# nuc10breakout.net
KiCad netlist of a schematic drawn in EAGLE
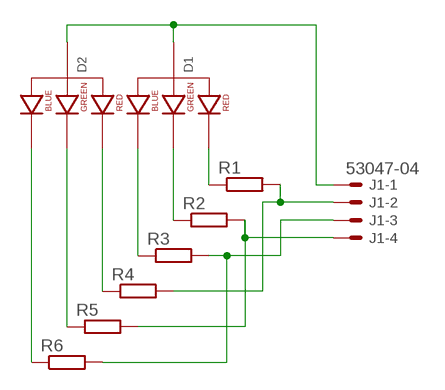
[diagram p0: schematic, sheet 1]

(export (version "E")
  (design (tool "Eeschema 10.0.6"))
  (components
    (comp (ref "D1")
      (value "LED-RGB-CA-THRUDIFFUSE")
      (footprint "eagle-import:LED-RGB-THRU")
      (libsource (lib "eagle-import") (part "LED-RGB-CA-THRUDIFFUSE"))
    )
    (comp (ref "D2")
      (value "LED-RGB-CA-THRUDIFFUSE")
      (footprint "eagle-import:LED-RGB-THRU")
      (libsource (lib "eagle-import") (part "LED-RGB-CA-THRUDIFFUSE"))
    )
    (comp (ref "J1")
      (value "53047-04")
      (footprint "eagle-import:53047-04")
      (fields (field (name "MF") "WALDOM/MOLEX") (field (name "MPN") "53047-0410"))
      (libsource (lib "eagle-import") (part "53?-04047"))
    )
    (comp (ref "R1")
      (value "R-EU_0204/5")
      (footprint "eagle-import:0204_5")
      (libsource (lib "eagle-import") (part "R-EU_0204/5"))
    )
    (comp (ref "R2")
      (value "R-EU_0204/5")
      (footprint "eagle-import:0204_5")
      (libsource (lib "eagle-import") (part "R-EU_0204/5"))
    )
    (comp (ref "R3")
      (value "R-EU_0204/5")
      (footprint "eagle-import:0204_5")
      (libsource (lib "eagle-import") (part "R-EU_0204/5"))
    )
    (comp (ref "R4")
      (value "R-EU_0204/5")
      (footprint "eagle-import:0204_5")
      (libsource (lib "eagle-import") (part "R-EU_0204/5"))
    )
    (comp (ref "R5")
      (value "R-EU_0204/5")
      (footprint "eagle-import:0204_5")
      (libsource (lib "eagle-import") (part "R-EU_0204/5"))
    )
    (comp (ref "R6")
      (value "R-EU_0204/5")
      (footprint "eagle-import:0204_5")
      (libsource (lib "eagle-import") (part "R-EU_0204/5"))
    )
  )
  (nets
    (net (code "1") (name "Net-(D1-ANODE)") (class "Default")
      (node (ref "D1") (pin "2") (pinfunction "ANODE_2") (pintype "bidirectional"))
      (node (ref "D2") (pin "2") (pinfunction "ANODE_2") (pintype "bidirectional"))
      (node (ref "J1") (pin "1") (pinfunction "S_1") (pintype "passive"))
    )
    (net (code "2") (name "Net-(D1-BLUE_CATHODE)") (class "Default")
      (node (ref "D1") (pin "4") (pinfunction "BLUE_CATHODE_4") (pintype "bidirectional"))
      (node (ref "R3") (pin "1") (pinfunction "1_1") (pintype "passive"))
    )
    (net (code "3") (name "Net-(D1-GREEN_CATHODE)") (class "Default")
      (node (ref "D1") (pin "3") (pinfunction "GREEN_CATHODE_3") (pintype "bidirectional"))
      (node (ref "R2") (pin "1") (pinfunction "1_1") (pintype "passive"))
    )
    (net (code "4") (name "Net-(D1-RED_CATHODE)") (class "Default")
      (node (ref "D1") (pin "1") (pinfunction "RED_CATHODE_1") (pintype "bidirectional"))
      (node (ref "R1") (pin "1") (pinfunction "1_1") (pintype "passive"))
    )
    (net (code "5") (name "Net-(D2-BLUE_CATHODE)") (class "Default")
      (node (ref "D2") (pin "4") (pinfunction "BLUE_CATHODE_4") (pintype "bidirectional"))
      (node (ref "R6") (pin "1") (pinfunction "1_1") (pintype "passive"))
    )
    (net (code "6") (name "Net-(D2-GREEN_CATHODE)") (class "Default")
      (node (ref "D2") (pin "3") (pinfunction "GREEN_CATHODE_3") (pintype "bidirectional"))
      (node (ref "R5") (pin "1") (pinfunction "1_1") (pintype "passive"))
    )
    (net (code "7") (name "Net-(D2-RED_CATHODE)") (class "Default")
      (node (ref "D2") (pin "1") (pinfunction "RED_CATHODE_1") (pintype "bidirectional"))
      (node (ref "R4") (pin "1") (pinfunction "1_1") (pintype "passive"))
    )
    (net (code "8") (name "Net-(J1B-S)") (class "Default")
      (node (ref "J1") (pin "2") (pinfunction "S_2") (pintype "passive"))
      (node (ref "R1") (pin "2") (pinfunction "2_2") (pintype "passive"))
      (node (ref "R4") (pin "2") (pinfunction "2_2") (pintype "passive"))
    )
    (net (code "9") (name "Net-(J1C-S)") (class "Default")
      (node (ref "J1") (pin "3") (pinfunction "S_3") (pintype "passive"))
      (node (ref "R3") (pin "2") (pinfunction "2_2") (pintype "passive"))
      (node (ref "R6") (pin "2") (pinfunction "2_2") (pintype "passive"))
    )
    (net (code "10") (name "Net-(J1D-S)") (class "Default")
      (node (ref "J1") (pin "4") (pinfunction "S_4") (pintype "passive"))
      (node (ref "R2") (pin "2") (pinfunction "2_2") (pintype "passive"))
      (node (ref "R5") (pin "2") (pinfunction "2_2") (pintype "passive"))
    )
  )
)
